# pmod-64x64-rgb-led-matrix-adapter.net
KiCad netlist of a schematic drawn in EAGLE
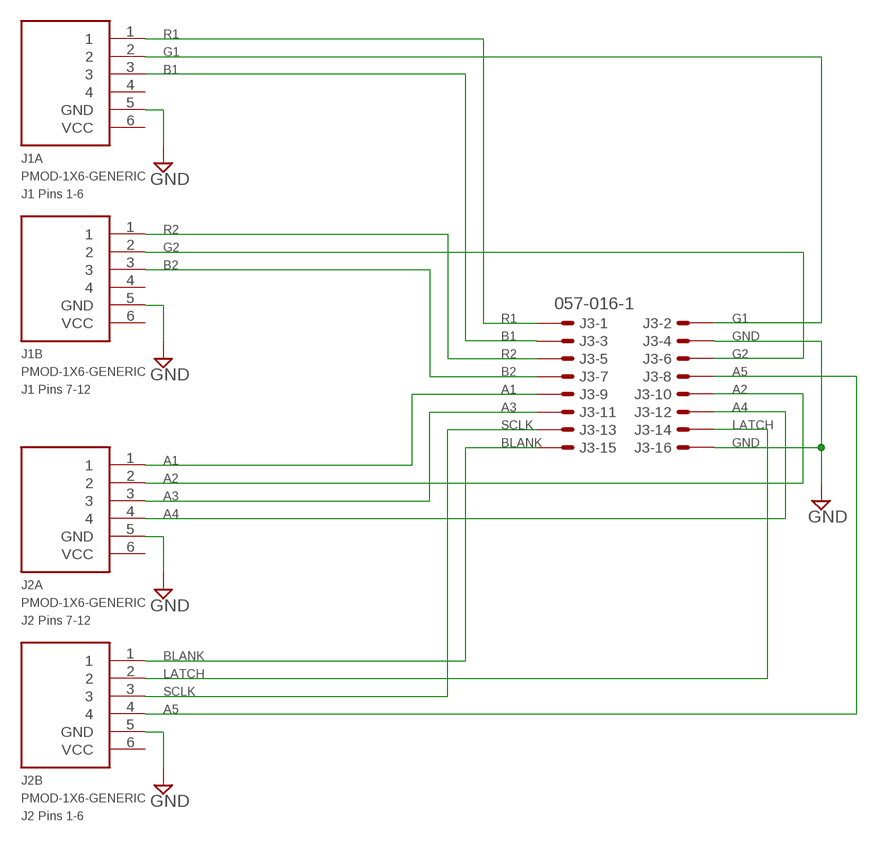
[diagram p0: schematic, sheet 1]

(export (version "E")
  (design (tool "Eeschema 10.0.6"))
  (components
    (comp (ref "J1A")
      (value "PMOD-1X6-GENERIC")
      (footprint "eagle-import:CON-PMOD-1X6")
      (libsource (lib "eagle-import") (part "PMOD-1X6-GENERIC"))
    )
    (comp (ref "J1B")
      (value "PMOD-1X6-GENERIC")
      (footprint "eagle-import:CON-PMOD-1X6")
      (libsource (lib "eagle-import") (part "PMOD-1X6-GENERIC"))
    )
    (comp (ref "J2A")
      (value "PMOD-1X6-GENERIC")
      (footprint "eagle-import:CON-PMOD-1X6")
      (libsource (lib "eagle-import") (part "PMOD-1X6-GENERIC"))
    )
    (comp (ref "J2B")
      (value "PMOD-1X6-GENERIC")
      (footprint "eagle-import:CON-PMOD-1X6")
      (libsource (lib "eagle-import") (part "PMOD-1X6-GENERIC"))
    )
    (comp (ref "J3")
      (value "057-016-1")
      (footprint "eagle-import:057-016-1")
      (libsource (lib "eagle-import") (part "057-016-1"))
    )
  )
  (nets
    (net (code "1") (name "/A1") (class "Default")
      (node (ref "J2A") (pin "1") (pinfunction "1_1") (pintype "bidirectional"))
      (node (ref "J3") (pin "9") (pinfunction "S_9") (pintype "passive"))
    )
    (net (code "2") (name "/A2") (class "Default")
      (node (ref "J2A") (pin "2") (pinfunction "2_2") (pintype "bidirectional"))
      (node (ref "J3") (pin "10") (pinfunction "S_10") (pintype "passive"))
    )
    (net (code "3") (name "/A3") (class "Default")
      (node (ref "J2A") (pin "3") (pinfunction "3_3") (pintype "bidirectional"))
      (node (ref "J3") (pin "11") (pinfunction "S_11") (pintype "passive"))
    )
    (net (code "4") (name "/A4") (class "Default")
      (node (ref "J2A") (pin "4") (pinfunction "4_4") (pintype "bidirectional"))
      (node (ref "J3") (pin "12") (pinfunction "S_12") (pintype "passive"))
    )
    (net (code "5") (name "/A5") (class "Default")
      (node (ref "J2B") (pin "4") (pinfunction "4_4") (pintype "bidirectional"))
      (node (ref "J3") (pin "8") (pinfunction "S_8") (pintype "passive"))
    )
    (net (code "6") (name "/B1") (class "Default")
      (node (ref "J1A") (pin "3") (pinfunction "3_3") (pintype "bidirectional"))
      (node (ref "J3") (pin "3") (pinfunction "S_3") (pintype "passive"))
    )
    (net (code "7") (name "/B2") (class "Default")
      (node (ref "J1B") (pin "3") (pinfunction "3_3") (pintype "bidirectional"))
      (node (ref "J3") (pin "7") (pinfunction "S_7") (pintype "passive"))
    )
    (net (code "8") (name "/BLANK") (class "Default")
      (node (ref "J2B") (pin "1") (pinfunction "1_1") (pintype "bidirectional"))
      (node (ref "J3") (pin "15") (pinfunction "S_15") (pintype "passive"))
    )
    (net (code "9") (name "/G1") (class "Default")
      (node (ref "J1A") (pin "2") (pinfunction "2_2") (pintype "bidirectional"))
      (node (ref "J3") (pin "2") (pinfunction "S_2") (pintype "passive"))
    )
    (net (code "10") (name "/G2") (class "Default")
      (node (ref "J1B") (pin "2") (pinfunction "2_2") (pintype "bidirectional"))
      (node (ref "J3") (pin "6") (pinfunction "S_6") (pintype "passive"))
    )
    (net (code "11") (name "/LATCH") (class "Default")
      (node (ref "J2B") (pin "2") (pinfunction "2_2") (pintype "bidirectional"))
      (node (ref "J3") (pin "14") (pinfunction "S_14") (pintype "passive"))
    )
    (net (code "12") (name "/R1") (class "Default")
      (node (ref "J1A") (pin "1") (pinfunction "1_1") (pintype "bidirectional"))
      (node (ref "J3") (pin "1") (pinfunction "S_1") (pintype "passive"))
    )
    (net (code "13") (name "/R2") (class "Default")
      (node (ref "J1B") (pin "1") (pinfunction "1_1") (pintype "bidirectional"))
      (node (ref "J3") (pin "5") (pinfunction "S_5") (pintype "passive"))
    )
    (net (code "14") (name "/SCLK") (class "Default")
      (node (ref "J2B") (pin "3") (pinfunction "3_3") (pintype "bidirectional"))
      (node (ref "J3") (pin "13") (pinfunction "S_13") (pintype "passive"))
    )
    (net (code "15") (name "GND") (class "Default")
      (node (ref "J1A") (pin "5") (pinfunction "GND_5") (pintype "power_in"))
      (node (ref "J1B") (pin "5") (pinfunction "GND_5") (pintype "power_in"))
      (node (ref "J2A") (pin "5") (pinfunction "GND_5") (pintype "power_in"))
      (node (ref "J2B") (pin "5") (pinfunction "GND_5") (pintype "power_in"))
      (node (ref "J3") (pin "16") (pinfunction "S_16") (pintype "passive"))
      (node (ref "J3") (pin "4") (pinfunction "S_4") (pintype "passive"))
    )
    (net (code "16") (name "unconnected-(J1A-Pad4)") (class "Default")
      (node (ref "J1A") (pin "4") (pinfunction "4_4") (pintype "bidirectional"))
    )
    (net (code "17") (name "unconnected-(J1A-VCC-Pad6)") (class "Default")
      (node (ref "J1A") (pin "6") (pinfunction "VCC_6") (pintype "bidirectional"))
    )
    (net (code "18") (name "unconnected-(J1B-Pad4)") (class "Default")
      (node (ref "J1B") (pin "4") (pinfunction "4_4") (pintype "bidirectional"))
    )
    (net (code "19") (name "unconnected-(J1B-VCC-Pad6)") (class "Default")
      (node (ref "J1B") (pin "6") (pinfunction "VCC_6") (pintype "bidirectional"))
    )
    (net (code "20") (name "unconnected-(J2A-VCC-Pad6)") (class "Default")
      (node (ref "J2A") (pin "6") (pinfunction "VCC_6") (pintype "bidirectional"))
    )
    (net (code "21") (name "unconnected-(J2B-VCC-Pad6)") (class "Default")
      (node (ref "J2B") (pin "6") (pinfunction "VCC_6") (pintype "bidirectional"))
    )
  )
)
